# lpc1114_LCD.net
KiCad netlist of a schematic drawn in EAGLE
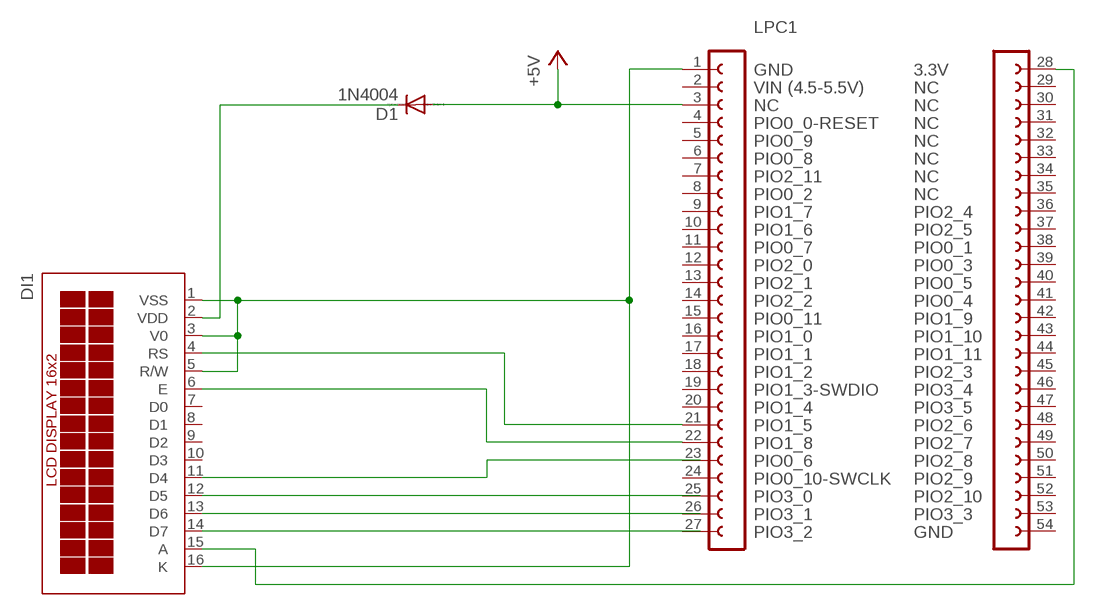
[diagram p0: schematic, sheet 1]

(export (version "E")
  (design (tool "Eeschema 10.0.6"))
  (components
    (comp (ref "D1")
      (value "1N4004")
      (footprint "eagle-import:DO41-10")
      (libsource (lib "eagle-import") (part "1N4004"))
    )
    (comp (ref "DI1")
      (value "DISPLAY_")
      (footprint "eagle-import:HD44780_PC")
      (libsource (lib "eagle-import") (part "DISPLAY_"))
    )
    (comp (ref "LPC1")
      (value "LPCXPRESSO_LPC1114")
      (footprint "eagle-import:LPCXPRESSO_LPC1114")
      (libsource (lib "eagle-import") (part "LPCXPRESSO_LPC1114"))
    )
  )
  (nets
    (net (code "1") (name "+5V") (class "Default")
      (node (ref "D1") (pin "A") (pinfunction "A_A") (pintype "passive"))
      (node (ref "LPC1") (pin "3") (pinfunction "3_3") (pintype "passive"))
    )
    (net (code "2") (name "Net-(DI1-A)") (class "Default")
      (node (ref "DI1") (pin "15") (pinfunction "A_15") (pintype "passive"))
      (node (ref "LPC1") (pin "28") (pinfunction "28_28") (pintype "passive"))
    )
    (net (code "3") (name "Net-(DI1-E)") (class "Default")
      (node (ref "DI1") (pin "6") (pinfunction "E_6") (pintype "input"))
      (node (ref "LPC1") (pin "22") (pinfunction "22_22") (pintype "passive"))
    )
    (net (code "4") (name "Net-(DI1-K)") (class "Default")
      (node (ref "DI1") (pin "1") (pinfunction "VSS_1") (pintype "power_in"))
      (node (ref "DI1") (pin "16") (pinfunction "K_16") (pintype "passive"))
      (node (ref "DI1") (pin "3") (pinfunction "V0_3") (pintype "power_in"))
      (node (ref "DI1") (pin "5") (pinfunction "R/W_5") (pintype "input"))
      (node (ref "LPC1") (pin "1") (pinfunction "1_1") (pintype "passive"))
    )
    (net (code "5") (name "Net-(DI1-RS)") (class "Default")
      (node (ref "DI1") (pin "4") (pinfunction "RS_4") (pintype "input"))
      (node (ref "LPC1") (pin "21") (pinfunction "21_21") (pintype "passive"))
    )
    (net (code "6") (name "Net-(DI1-VDD)") (class "Default")
      (node (ref "D1") (pin "C") (pinfunction "C_C") (pintype "passive"))
      (node (ref "DI1") (pin "2") (pinfunction "VDD_2") (pintype "power_in"))
    )
    (net (code "7") (name "unconnected-(DI1-D0-Pad7)") (class "Default")
      (node (ref "DI1") (pin "7") (pinfunction "D0_7") (pintype "input"))
    )
    (net (code "8") (name "unconnected-(DI1-D1-Pad8)") (class "Default")
      (node (ref "DI1") (pin "8") (pinfunction "D1_8") (pintype "input"))
    )
    (net (code "9") (name "unconnected-(DI1-D2-Pad9)") (class "Default")
      (node (ref "DI1") (pin "9") (pinfunction "D2_9") (pintype "input"))
    )
    (net (code "10") (name "unconnected-(DI1-D3-Pad10)") (class "Default")
      (node (ref "DI1") (pin "10") (pinfunction "D3_10") (pintype "input"))
    )
    (net (code "11") (name "unconnected-(DI1-D4-Pad11)") (class "Default")
      (node (ref "DI1") (pin "11") (pinfunction "D4_11") (pintype "input"))
    )
    (net (code "12") (name "unconnected-(DI1-D5-Pad12)") (class "Default")
      (node (ref "DI1") (pin "12") (pinfunction "D5_12") (pintype "input"))
    )
    (net (code "13") (name "unconnected-(DI1-D6-Pad13)") (class "Default")
      (node (ref "DI1") (pin "13") (pinfunction "D6_13") (pintype "input"))
    )
    (net (code "14") (name "unconnected-(DI1-D7-Pad14)") (class "Default")
      (node (ref "DI1") (pin "14") (pinfunction "D7_14") (pintype "input"))
    )
    (net (code "15") (name "unconnected-(LPC1-Pad2)") (class "Default")
      (node (ref "LPC1") (pin "2") (pinfunction "2_2") (pintype "passive"))
    )
    (net (code "16") (name "unconnected-(LPC1-Pad4)") (class "Default")
      (node (ref "LPC1") (pin "4") (pinfunction "4_4") (pintype "passive"))
    )
    (net (code "17") (name "unconnected-(LPC1-Pad5)") (class "Default")
      (node (ref "LPC1") (pin "5") (pinfunction "5_5") (pintype "passive"))
    )
    (net (code "18") (name "unconnected-(LPC1-Pad6)") (class "Default")
      (node (ref "LPC1") (pin "6") (pinfunction "6_6") (pintype "passive"))
    )
    (net (code "19") (name "unconnected-(LPC1-Pad7)") (class "Default")
      (node (ref "LPC1") (pin "7") (pinfunction "7_7") (pintype "passive"))
    )
    (net (code "20") (name "unconnected-(LPC1-Pad8)") (class "Default")
      (node (ref "LPC1") (pin "8") (pinfunction "8_8") (pintype "passive"))
    )
    (net (code "21") (name "unconnected-(LPC1-Pad9)") (class "Default")
      (node (ref "LPC1") (pin "9") (pinfunction "9_9") (pintype "passive"))
    )
    (net (code "22") (name "unconnected-(LPC1-Pad10)") (class "Default")
      (node (ref "LPC1") (pin "10") (pinfunction "10_10") (pintype "passive"))
    )
    (net (code "23") (name "unconnected-(LPC1-Pad11)") (class "Default")
      (node (ref "LPC1") (pin "11") (pinfunction "11_11") (pintype "passive"))
    )
    (net (code "24") (name "unconnected-(LPC1-Pad12)") (class "Default")
      (node (ref "LPC1") (pin "12") (pinfunction "12_12") (pintype "passive"))
    )
    (net (code "25") (name "unconnected-(LPC1-Pad13)") (class "Default")
      (node (ref "LPC1") (pin "13") (pinfunction "13_13") (pintype "passive"))
    )
    (net (code "26") (name "unconnected-(LPC1-Pad14)") (class "Default")
      (node (ref "LPC1") (pin "14") (pinfunction "14_14") (pintype "passive"))
    )
    (net (code "27") (name "unconnected-(LPC1-Pad15)") (class "Default")
      (node (ref "LPC1") (pin "15") (pinfunction "15_15") (pintype "passive"))
    )
    (net (code "28") (name "unconnected-(LPC1-Pad16)") (class "Default")
      (node (ref "LPC1") (pin "16") (pinfunction "16_16") (pintype "passive"))
    )
    (net (code "29") (name "unconnected-(LPC1-Pad17)") (class "Default")
      (node (ref "LPC1") (pin "17") (pinfunction "17_17") (pintype "passive"))
    )
    (net (code "30") (name "unconnected-(LPC1-Pad18)") (class "Default")
      (node (ref "LPC1") (pin "18") (pinfunction "18_18") (pintype "passive"))
    )
    (net (code "31") (name "unconnected-(LPC1-Pad19)") (class "Default")
      (node (ref "LPC1") (pin "19") (pinfunction "19_19") (pintype "passive"))
    )
    (net (code "32") (name "unconnected-(LPC1-Pad20)") (class "Default")
      (node (ref "LPC1") (pin "20") (pinfunction "20_20") (pintype "passive"))
    )
    (net (code "33") (name "unconnected-(LPC1-Pad23)") (class "Default")
      (node (ref "LPC1") (pin "23") (pinfunction "23_23") (pintype "passive"))
    )
    (net (code "34") (name "unconnected-(LPC1-Pad24)") (class "Default")
      (node (ref "LPC1") (pin "24") (pinfunction "24_24") (pintype "passive"))
    )
    (net (code "35") (name "unconnected-(LPC1-Pad25)") (class "Default")
      (node (ref "LPC1") (pin "25") (pinfunction "25_25") (pintype "passive"))
    )
    (net (code "36") (name "unconnected-(LPC1-Pad26)") (class "Default")
      (node (ref "LPC1") (pin "26") (pinfunction "26_26") (pintype "passive"))
    )
    (net (code "37") (name "unconnected-(LPC1-Pad27)") (class "Default")
      (node (ref "LPC1") (pin "27") (pinfunction "27_27") (pintype "passive"))
    )
    (net (code "38") (name "unconnected-(LPC1-Pad29)") (class "Default")
      (node (ref "LPC1") (pin "29") (pinfunction "29_29") (pintype "passive"))
    )
    (net (code "39") (name "unconnected-(LPC1-Pad30)") (class "Default")
      (node (ref "LPC1") (pin "30") (pinfunction "30_30") (pintype "passive"))
    )
    (net (code "40") (name "unconnected-(LPC1-Pad31)") (class "Default")
      (node (ref "LPC1") (pin "31") (pinfunction "31_31") (pintype "passive"))
    )
    (net (code "41") (name "unconnected-(LPC1-Pad32)") (class "Default")
      (node (ref "LPC1") (pin "32") (pinfunction "32_32") (pintype "passive"))
    )
    (net (code "42") (name "unconnected-(LPC1-Pad33)") (class "Default")
      (node (ref "LPC1") (pin "33") (pinfunction "33_33") (pintype "passive"))
    )
    (net (code "43") (name "unconnected-(LPC1-Pad34)") (class "Default")
      (node (ref "LPC1") (pin "34") (pinfunction "34_34") (pintype "passive"))
    )
    (net (code "44") (name "unconnected-(LPC1-Pad35)") (class "Default")
      (node (ref "LPC1") (pin "35") (pinfunction "35_35") (pintype "passive"))
    )
    (net (code "45") (name "unconnected-(LPC1-Pad36)") (class "Default")
      (node (ref "LPC1") (pin "36") (pinfunction "36_36") (pintype "passive"))
    )
    (net (code "46") (name "unconnected-(LPC1-Pad37)") (class "Default")
      (node (ref "LPC1") (pin "37") (pinfunction "37_37") (pintype "passive"))
    )
    (net (code "47") (name "unconnected-(LPC1-Pad38)") (class "Default")
      (node (ref "LPC1") (pin "38") (pinfunction "38_38") (pintype "passive"))
    )
    (net (code "48") (name "unconnected-(LPC1-Pad39)") (class "Default")
      (node (ref "LPC1") (pin "39") (pinfunction "39_39") (pintype "passive"))
    )
    (net (code "49") (name "unconnected-(LPC1-Pad40)") (class "Default")
      (node (ref "LPC1") (pin "40") (pinfunction "40_40") (pintype "passive"))
    )
    (net (code "50") (name "unconnected-(LPC1-Pad41)") (class "Default")
      (node (ref "LPC1") (pin "41") (pinfunction "41_41") (pintype "passive"))
    )
    (net (code "51") (name "unconnected-(LPC1-Pad42)") (class "Default")
      (node (ref "LPC1") (pin "42") (pinfunction "42_42") (pintype "passive"))
    )
    (net (code "52") (name "unconnected-(LPC1-Pad43)") (class "Default")
      (node (ref "LPC1") (pin "43") (pinfunction "43_43") (pintype "passive"))
    )
    (net (code "53") (name "unconnected-(LPC1-Pad44)") (class "Default")
      (node (ref "LPC1") (pin "44") (pinfunction "44_44") (pintype "passive"))
    )
    (net (code "54") (name "unconnected-(LPC1-Pad45)") (class "Default")
      (node (ref "LPC1") (pin "45") (pinfunction "45_45") (pintype "passive"))
    )
    (net (code "55") (name "unconnected-(LPC1-Pad46)") (class "Default")
      (node (ref "LPC1") (pin "46") (pinfunction "46_46") (pintype "passive"))
    )
    (net (code "56") (name "unconnected-(LPC1-Pad47)") (class "Default")
      (node (ref "LPC1") (pin "47") (pinfunction "47_47") (pintype "passive"))
    )
    (net (code "57") (name "unconnected-(LPC1-Pad48)") (class "Default")
      (node (ref "LPC1") (pin "48") (pinfunction "48_48") (pintype "passive"))
    )
    (net (code "58") (name "unconnected-(LPC1-Pad49)") (class "Default")
      (node (ref "LPC1") (pin "49") (pinfunction "49_49") (pintype "passive"))
    )
    (net (code "59") (name "unconnected-(LPC1-Pad50)") (class "Default")
      (node (ref "LPC1") (pin "50") (pinfunction "50_50") (pintype "passive"))
    )
    (net (code "60") (name "unconnected-(LPC1-Pad51)") (class "Default")
      (node (ref "LPC1") (pin "51") (pinfunction "51_51") (pintype "passive"))
    )
    (net (code "61") (name "unconnected-(LPC1-Pad52)") (class "Default")
      (node (ref "LPC1") (pin "52") (pinfunction "52_52") (pintype "passive"))
    )
    (net (code "62") (name "unconnected-(LPC1-Pad53)") (class "Default")
      (node (ref "LPC1") (pin "53") (pinfunction "53_53") (pintype "passive"))
    )
    (net (code "63") (name "unconnected-(LPC1-Pad54)") (class "Default")
      (node (ref "LPC1") (pin "54") (pinfunction "54_54") (pintype "passive"))
    )
  )
)
